# cam_switch.net
KiCad netlist of a schematic drawn in EAGLE
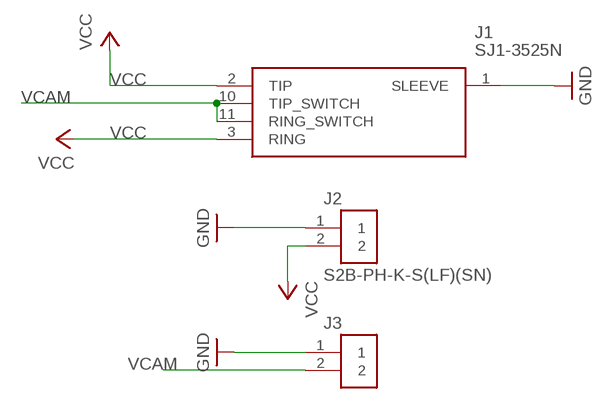
[diagram p0: schematic, sheet 1]

(export (version "E")
  (design (tool "Eeschema 10.0.6"))
  (components
    (comp (ref "J1")
      (value "SJ1-3525N")
      (footprint "eagle-import:SJ13525N")
      (libsource (lib "eagle-import") (part "SJ1-3525N"))
    )
    (comp (ref "J2")
      (value "S2B-PH-K-S(LF)(SN)")
      (footprint "eagle-import:S2B-PH-K-S(LF)(SN)")
      (fields
        (field (name "DIGI_KEY_PART_NUMBER") "455-1719-ND")
        (field (name "MANUFACTURER") "JST Sales America Inc.")
        (field (name "CREATED_BY") "PCBLayout.com")
      )
      (libsource (lib "eagle-import") (part "S2B-PH-K-S(LF)(SN)"))
    )
    (comp (ref "J3")
      (value "S2B-PH-K-S(LF)(SN)")
      (footprint "eagle-import:S2B-PH-K-S(LF)(SN)")
      (fields
        (field (name "DIGI_KEY_PART_NUMBER") "455-1719-ND")
        (field (name "MANUFACTURER") "JST Sales America Inc.")
        (field (name "CREATED_BY") "PCBLayout.com")
      )
      (libsource (lib "eagle-import") (part "S2B-PH-K-S(LF)(SN)"))
    )
  )
  (nets
    (net (code "1") (name "/VCAM") (class "Default")
      (node (ref "J1") (pin "10") (pinfunction "TIP_SWITCH_10") (pintype "bidirectional"))
      (node (ref "J1") (pin "11") (pinfunction "RING_SWITCH_11") (pintype "bidirectional"))
      (node (ref "J3") (pin "2") (pinfunction "2_2") (pintype "passive"))
    )
    (net (code "2") (name "GND") (class "Default")
      (node (ref "J1") (pin "1") (pinfunction "SLEEVE_1") (pintype "bidirectional"))
      (node (ref "J2") (pin "1") (pinfunction "1_1") (pintype "passive"))
      (node (ref "J3") (pin "1") (pinfunction "1_1") (pintype "passive"))
    )
    (net (code "3") (name "VCC") (class "Default")
      (node (ref "J1") (pin "2") (pinfunction "TIP_2") (pintype "bidirectional"))
      (node (ref "J1") (pin "3") (pinfunction "RING_3") (pintype "bidirectional"))
      (node (ref "J2") (pin "2") (pinfunction "2_2") (pintype "passive"))
    )
  )
)
